# soqueteESP32.net
KiCad netlist of a schematic drawn in Altium Designer
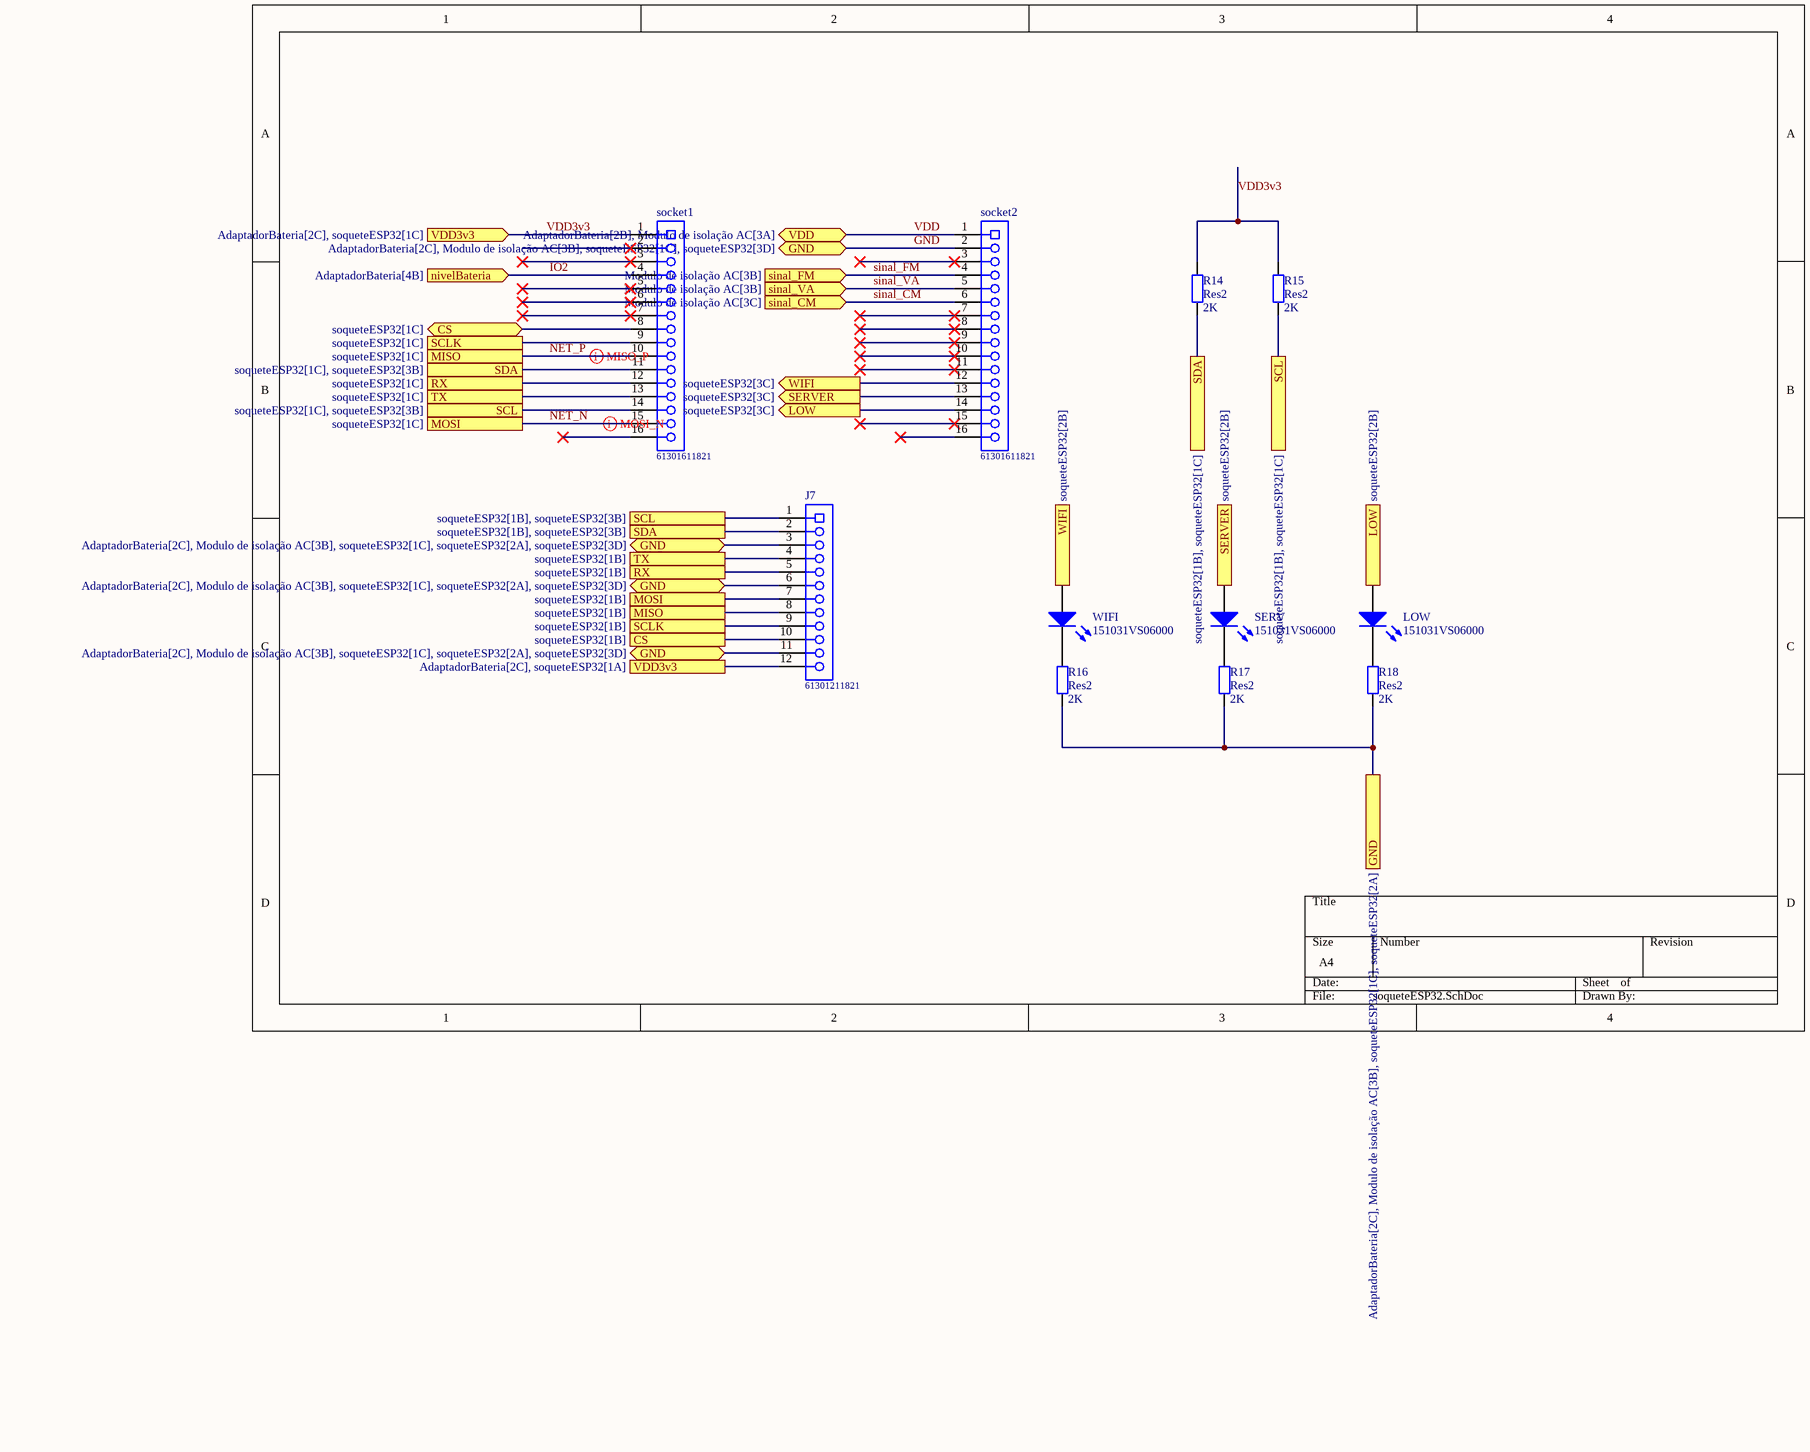
[diagram p0: soqueteESP32.SchDoc]

(export (version "E")
  (design (tool "Eeschema 10.0.6"))
  (components
    (comp (ref "J7")
      (value "61301211821")
      (footprint "61301211821")
      (description "THT Vertical Socket Header WR-PHD, Pitch 2.54 mm, Single Row, 12 pins")
      (fields (field (name "MANUFACTURER") "Wurth Elektronik") (field (name "PUBLISHER") "WurthElektronik"))
      (libsource (lib "Altium Content Vault") (part "WE-CN-1P-F-R12"))
    )
    (comp (ref "LOW")
      (value "151031VS06000")
      (footprint "Type 3mm")
      (description "THT LED round mono-color color lens, WL-TMRC , Bright Green")
      (fields (field (name "MANUFACTURER") "Wuerth Elektronik"))
      (libsource (lib "Altium Content Vault") (part "WE-LED_K1A2-2"))
    )
    (comp (ref "R14")
      (value "Res2")
      (footprint "AXIAL-0.4")
      (description "Resistor")
      (fields (field (name "ALTIUM_VALUE") "2K") (field (name "PUBLISHER") "Altium Limited"))
      (libsource (lib "Miscellaneous Devices") (part "Res2"))
    )
    (comp (ref "R15")
      (value "Res2")
      (footprint "AXIAL-0.4")
      (description "Resistor")
      (fields (field (name "ALTIUM_VALUE") "2K") (field (name "PUBLISHER") "Altium Limited"))
      (libsource (lib "Miscellaneous Devices") (part "Res2"))
    )
    (comp (ref "R16")
      (value "Res2")
      (footprint "AXIAL-0.4")
      (description "Resistor")
      (fields (field (name "ALTIUM_VALUE") "2K") (field (name "PUBLISHER") "Altium Limited"))
      (libsource (lib "Miscellaneous Devices") (part "Res2"))
    )
    (comp (ref "R17")
      (value "Res2")
      (footprint "AXIAL-0.4")
      (description "Resistor")
      (fields (field (name "ALTIUM_VALUE") "2K") (field (name "PUBLISHER") "Altium Limited"))
      (libsource (lib "Miscellaneous Devices") (part "Res2"))
    )
    (comp (ref "R18")
      (value "Res2")
      (footprint "AXIAL-0.4")
      (description "Resistor")
      (fields (field (name "ALTIUM_VALUE") "2K") (field (name "PUBLISHER") "Altium Limited"))
      (libsource (lib "Miscellaneous Devices") (part "Res2"))
    )
    (comp (ref "SERV")
      (value "151031VS06000")
      (footprint "Type 3mm")
      (description "THT LED round mono-color color lens, WL-TMRC , Bright Green")
      (fields (field (name "MANUFACTURER") "Wuerth Elektronik"))
      (libsource (lib "Altium Content Vault") (part "WE-LED_K1A2-2"))
    )
    (comp (ref "socket1")
      (value "61301611821")
      (footprint "61301611821")
      (description "THT Vertical Socket Header WR-PHD, Pitch 2.54 mm, Single Row, 16 pins")
      (fields (field (name "MANUFACTURER") "Wurth Elektronik") (field (name "PUBLISHER") "WurthElektronik"))
      (libsource (lib "Altium Content Vault") (part "WE-CN-1P-F-R16"))
    )
    (comp (ref "socket2")
      (value "61301611821")
      (footprint "61301611821")
      (description "THT Vertical Socket Header WR-PHD, Pitch 2.54 mm, Single Row, 16 pins")
      (fields (field (name "MANUFACTURER") "Wurth Elektronik") (field (name "PUBLISHER") "WurthElektronik"))
      (libsource (lib "Altium Content Vault") (part "WE-CN-1P-F-R16"))
    )
    (comp (ref "WIFI")
      (value "151031VS06000")
      (footprint "Type 3mm")
      (description "THT LED round mono-color color lens, WL-TMRC , Bright Green")
      (fields (field (name "MANUFACTURER") "Wuerth Elektronik"))
      (libsource (lib "Altium Content Vault") (part "WE-LED_K1A2-2"))
    )
  )
  (nets
    (net (code "1") (name "/CS") (class "Default")
      (node (ref "J7") (pin "10") (pinfunction "10_10") (pintype "passive"))
      (node (ref "socket1") (pin "8") (pinfunction "8_8") (pintype "passive"))
    )
    (net (code "2") (name "/GND") (class "Default")
      (node (ref "J7") (pin "11") (pinfunction "11_11") (pintype "passive"))
      (node (ref "J7") (pin "3") (pinfunction "3_3") (pintype "passive"))
      (node (ref "J7") (pin "6") (pinfunction "6_6") (pintype "passive"))
      (node (ref "R16") (pin "1") (pinfunction "1_1") (pintype "passive"))
      (node (ref "R17") (pin "1") (pinfunction "1_1") (pintype "passive"))
      (node (ref "R18") (pin "1") (pinfunction "1_1") (pintype "passive"))
      (node (ref "socket2") (pin "2") (pinfunction "2_2") (pintype "passive"))
    )
    (net (code "3") (name "/IO2") (class "Default")
      (node (ref "socket1") (pin "4") (pinfunction "4_4") (pintype "passive"))
    )
    (net (code "4") (name "/LOW") (class "Default")
      (node (ref "LOW") (pin "2") (pinfunction "A_2") (pintype "passive"))
      (node (ref "socket2") (pin "14") (pinfunction "14_14") (pintype "passive"))
    )
    (net (code "5") (name "/NET_N") (class "Default")
      (node (ref "J7") (pin "7") (pinfunction "7_7") (pintype "passive"))
      (node (ref "socket1") (pin "15") (pinfunction "15_15") (pintype "passive"))
    )
    (net (code "6") (name "/NET_P") (class "Default")
      (node (ref "J7") (pin "8") (pinfunction "8_8") (pintype "passive"))
      (node (ref "socket1") (pin "10") (pinfunction "10_10") (pintype "passive"))
    )
    (net (code "7") (name "/RX") (class "Default")
      (node (ref "J7") (pin "5") (pinfunction "5_5") (pintype "passive"))
      (node (ref "socket1") (pin "12") (pinfunction "12_12") (pintype "passive"))
    )
    (net (code "8") (name "/SCL") (class "Default")
      (node (ref "J7") (pin "1") (pinfunction "1_1") (pintype "passive"))
      (node (ref "R15") (pin "1") (pinfunction "1_1") (pintype "passive"))
      (node (ref "socket1") (pin "14") (pinfunction "14_14") (pintype "passive"))
    )
    (net (code "9") (name "/SCLK") (class "Default")
      (node (ref "J7") (pin "9") (pinfunction "9_9") (pintype "passive"))
      (node (ref "socket1") (pin "9") (pinfunction "9_9") (pintype "passive"))
    )
    (net (code "10") (name "/SDA") (class "Default")
      (node (ref "J7") (pin "2") (pinfunction "2_2") (pintype "passive"))
      (node (ref "R14") (pin "1") (pinfunction "1_1") (pintype "passive"))
      (node (ref "socket1") (pin "11") (pinfunction "11_11") (pintype "passive"))
    )
    (net (code "11") (name "/SERVER") (class "Default")
      (node (ref "SERV") (pin "2") (pinfunction "A_2") (pintype "passive"))
      (node (ref "socket2") (pin "13") (pinfunction "13_13") (pintype "passive"))
    )
    (net (code "12") (name "/TX") (class "Default")
      (node (ref "J7") (pin "4") (pinfunction "4_4") (pintype "passive"))
      (node (ref "socket1") (pin "13") (pinfunction "13_13") (pintype "passive"))
    )
    (net (code "13") (name "/VDD") (class "Default")
      (node (ref "socket2") (pin "1") (pinfunction "1_1") (pintype "passive"))
    )
    (net (code "14") (name "/VDD3v3") (class "Default")
      (node (ref "J7") (pin "12") (pinfunction "12_12") (pintype "passive"))
      (node (ref "R14") (pin "2") (pinfunction "2_2") (pintype "passive"))
      (node (ref "R15") (pin "2") (pinfunction "2_2") (pintype "passive"))
      (node (ref "socket1") (pin "1") (pinfunction "1_1") (pintype "passive"))
    )
    (net (code "15") (name "/WIFI") (class "Default")
      (node (ref "WIFI") (pin "2") (pinfunction "A_2") (pintype "passive"))
      (node (ref "socket2") (pin "12") (pinfunction "12_12") (pintype "passive"))
    )
    (net (code "16") (name "/sinal_CM") (class "Default")
      (node (ref "socket2") (pin "6") (pinfunction "6_6") (pintype "passive"))
    )
    (net (code "17") (name "/sinal_FM") (class "Default")
      (node (ref "socket2") (pin "4") (pinfunction "4_4") (pintype "passive"))
    )
    (net (code "18") (name "/sinal_VA") (class "Default")
      (node (ref "socket2") (pin "5") (pinfunction "5_5") (pintype "passive"))
    )
    (net (code "19") (name "Net-(LOW-K)") (class "Default")
      (node (ref "LOW") (pin "1") (pinfunction "K_1") (pintype "passive"))
      (node (ref "R18") (pin "2") (pinfunction "2_2") (pintype "passive"))
    )
    (net (code "20") (name "Net-(SERV-K)") (class "Default")
      (node (ref "R17") (pin "2") (pinfunction "2_2") (pintype "passive"))
      (node (ref "SERV") (pin "1") (pinfunction "K_1") (pintype "passive"))
    )
    (net (code "21") (name "Net-(WIFI-K)") (class "Default")
      (node (ref "R16") (pin "2") (pinfunction "2_2") (pintype "passive"))
      (node (ref "WIFI") (pin "1") (pinfunction "K_1") (pintype "passive"))
    )
    (net (code "22") (name "unconnected-(socket1-Pad2)") (class "Default")
      (node (ref "socket1") (pin "2") (pinfunction "2_2") (pintype "passive+no_connect"))
    )
    (net (code "23") (name "unconnected-(socket1-Pad3)") (class "Default")
      (node (ref "socket1") (pin "3") (pinfunction "3_3") (pintype "passive+no_connect"))
    )
    (net (code "24") (name "unconnected-(socket1-Pad5)") (class "Default")
      (node (ref "socket1") (pin "5") (pinfunction "5_5") (pintype "passive+no_connect"))
    )
    (net (code "25") (name "unconnected-(socket1-Pad6)") (class "Default")
      (node (ref "socket1") (pin "6") (pinfunction "6_6") (pintype "passive+no_connect"))
    )
    (net (code "26") (name "unconnected-(socket1-Pad7)") (class "Default")
      (node (ref "socket1") (pin "7") (pinfunction "7_7") (pintype "passive+no_connect"))
    )
    (net (code "27") (name "unconnected-(socket1-Pad16)") (class "Default")
      (node (ref "socket1") (pin "16") (pinfunction "16_16") (pintype "passive+no_connect"))
    )
    (net (code "28") (name "unconnected-(socket2-Pad3)") (class "Default")
      (node (ref "socket2") (pin "3") (pinfunction "3_3") (pintype "passive+no_connect"))
    )
    (net (code "29") (name "unconnected-(socket2-Pad7)") (class "Default")
      (node (ref "socket2") (pin "7") (pinfunction "7_7") (pintype "passive+no_connect"))
    )
    (net (code "30") (name "unconnected-(socket2-Pad8)") (class "Default")
      (node (ref "socket2") (pin "8") (pinfunction "8_8") (pintype "passive+no_connect"))
    )
    (net (code "31") (name "unconnected-(socket2-Pad9)") (class "Default")
      (node (ref "socket2") (pin "9") (pinfunction "9_9") (pintype "passive+no_connect"))
    )
    (net (code "32") (name "unconnected-(socket2-Pad10)") (class "Default")
      (node (ref "socket2") (pin "10") (pinfunction "10_10") (pintype "passive+no_connect"))
    )
    (net (code "33") (name "unconnected-(socket2-Pad11)") (class "Default")
      (node (ref "socket2") (pin "11") (pinfunction "11_11") (pintype "passive+no_connect"))
    )
    (net (code "34") (name "unconnected-(socket2-Pad15)") (class "Default")
      (node (ref "socket2") (pin "15") (pinfunction "15_15") (pintype "passive+no_connect"))
    )
    (net (code "35") (name "unconnected-(socket2-Pad16)") (class "Default")
      (node (ref "socket2") (pin "16") (pinfunction "16_16") (pintype "passive+no_connect"))
    )
  )
)
